# ADC_MUX.net
KiCad netlist of a schematic drawn in Altium Designer
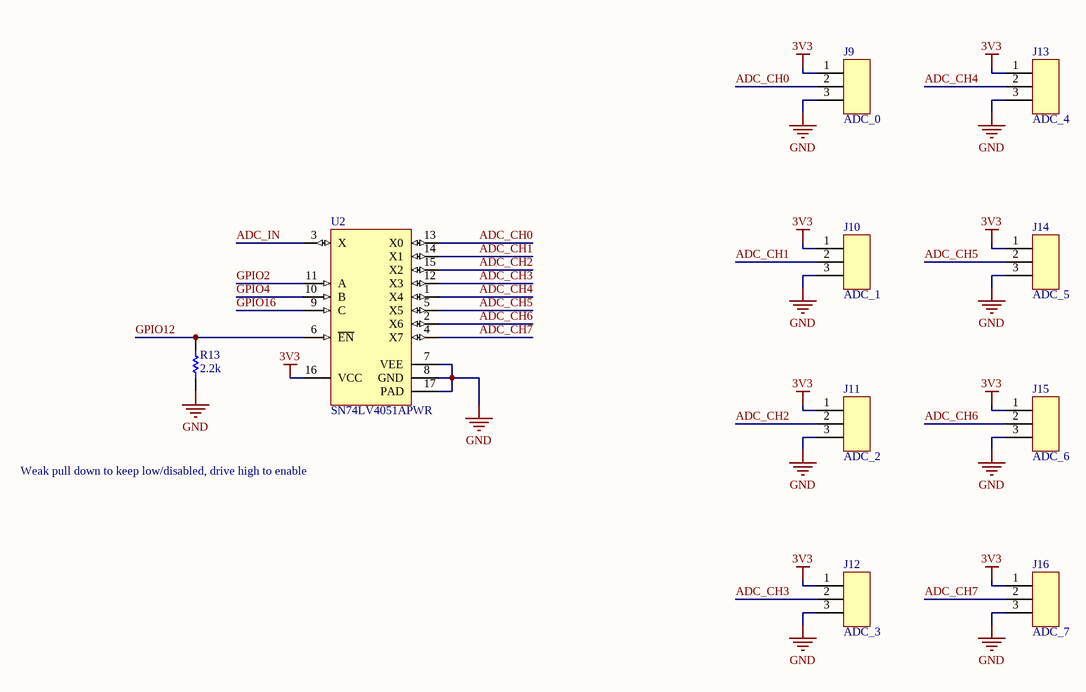
[diagram p0: ADC_MUX.SchDoc]

(export (version "E")
  (design (tool "Eeschema 10.0.6"))
  (components
    (comp (ref "J9")
      (value "ADC_0")
      (footprint "PCB-s0hfil65plaomi4ibvcw-1")
      (description "THT Vertical Pin Header WR-PHD, Pitch 2.54 mm, Single Row, 3 pins")
      (libsource (lib "CommunityVault") (part "SYM-8a90426ffa175557-17"))
    )
    (comp (ref "J10")
      (value "ADC_1")
      (footprint "PCB-s0hfil65plaomi4ibvcw-1")
      (description "THT Vertical Pin Header WR-PHD, Pitch 2.54 mm, Single Row, 3 pins")
      (libsource (lib "CommunityVault") (part "SYM-8a90426ffa175557-17"))
    )
    (comp (ref "J11")
      (value "ADC_2")
      (footprint "PCB-s0hfil65plaomi4ibvcw-1")
      (description "THT Vertical Pin Header WR-PHD, Pitch 2.54 mm, Single Row, 3 pins")
      (libsource (lib "CommunityVault") (part "SYM-8a90426ffa175557-17"))
    )
    (comp (ref "J12")
      (value "ADC_3")
      (footprint "PCB-s0hfil65plaomi4ibvcw-1")
      (description "THT Vertical Pin Header WR-PHD, Pitch 2.54 mm, Single Row, 3 pins")
      (libsource (lib "CommunityVault") (part "SYM-8a90426ffa175557-17"))
    )
    (comp (ref "J13")
      (value "ADC_4")
      (footprint "PCB-s0hfil65plaomi4ibvcw-1")
      (description "THT Vertical Pin Header WR-PHD, Pitch 2.54 mm, Single Row, 3 pins")
      (libsource (lib "CommunityVault") (part "SYM-8a90426ffa175557-17"))
    )
    (comp (ref "J14")
      (value "ADC_5")
      (footprint "PCB-s0hfil65plaomi4ibvcw-1")
      (description "THT Vertical Pin Header WR-PHD, Pitch 2.54 mm, Single Row, 3 pins")
      (libsource (lib "CommunityVault") (part "SYM-8a90426ffa175557-17"))
    )
    (comp (ref "J15")
      (value "ADC_6")
      (footprint "PCB-s0hfil65plaomi4ibvcw-1")
      (description "THT Vertical Pin Header WR-PHD, Pitch 2.54 mm, Single Row, 3 pins")
      (libsource (lib "CommunityVault") (part "SYM-8a90426ffa175557-17"))
    )
    (comp (ref "J16")
      (value "ADC_7")
      (footprint "PCB-s0hfil65plaomi4ibvcw-1")
      (description "THT Vertical Pin Header WR-PHD, Pitch 2.54 mm, Single Row, 3 pins")
      (libsource (lib "CommunityVault") (part "SYM-8a90426ffa175557-17"))
    )
    (comp (ref "R13")
      (value "2.2k")
      (footprint "PCB-2t5lv6a742zfbi3344hk-1")
      (description "Res, AEC-Q200, Thick Film, 2K2, 5%, 0603")
      (fields (field (name "MANUFACTURER PART NUMBER") "CRGCQ0603J2K2"))
      (libsource (lib "CommunityVault") (part "SYM-ce770211389311b0-1"))
    )
    (comp (ref "U2")
      (value "SN74LV4051APWR")
      (footprint "PCB-s2tlwx05pg4l7j3eq4ax-1")
      (description "5-V, 8: 1, 1-channel general-purpose analog multiplexer 16-TSSOP -40 to 85")
      (libsource (lib "FavoritesLibrary") (part "SYM-2f9ae6973f1af05d-2"))
    )
  )
  (nets
    (net (code "1") (name "/ADC_CH0") (class "Default")
      (node (ref "J9") (pin "2") (pinfunction "2_2") (pintype "passive"))
      (node (ref "U2") (pin "13") (pinfunction "X0_13") (pintype "bidirectional"))
    )
    (net (code "2") (name "/ADC_CH1") (class "Default")
      (node (ref "J10") (pin "2") (pinfunction "2_2") (pintype "passive"))
      (node (ref "U2") (pin "14") (pinfunction "X1_14") (pintype "bidirectional"))
    )
    (net (code "3") (name "/ADC_CH2") (class "Default")
      (node (ref "J11") (pin "2") (pinfunction "2_2") (pintype "passive"))
      (node (ref "U2") (pin "15") (pinfunction "X2_15") (pintype "bidirectional"))
    )
    (net (code "4") (name "/ADC_CH3") (class "Default")
      (node (ref "J12") (pin "2") (pinfunction "2_2") (pintype "passive"))
      (node (ref "U2") (pin "12") (pinfunction "X3_12") (pintype "bidirectional"))
    )
    (net (code "5") (name "/ADC_CH4") (class "Default")
      (node (ref "J13") (pin "2") (pinfunction "2_2") (pintype "passive"))
      (node (ref "U2") (pin "1") (pinfunction "X4_1") (pintype "bidirectional"))
    )
    (net (code "6") (name "/ADC_CH5") (class "Default")
      (node (ref "J14") (pin "2") (pinfunction "2_2") (pintype "passive"))
      (node (ref "U2") (pin "5") (pinfunction "X5_5") (pintype "bidirectional"))
    )
    (net (code "7") (name "/ADC_CH6") (class "Default")
      (node (ref "J15") (pin "2") (pinfunction "2_2") (pintype "passive"))
      (node (ref "U2") (pin "2") (pinfunction "X6_2") (pintype "bidirectional"))
    )
    (net (code "8") (name "/ADC_CH7") (class "Default")
      (node (ref "J16") (pin "2") (pinfunction "2_2") (pintype "passive"))
      (node (ref "U2") (pin "4") (pinfunction "X7_4") (pintype "bidirectional"))
    )
    (net (code "9") (name "/ADC_IN") (class "Default")
      (node (ref "U2") (pin "3") (pinfunction "X_3") (pintype "bidirectional"))
    )
    (net (code "10") (name "/GPIO2") (class "Default")
      (node (ref "U2") (pin "11") (pinfunction "A_11") (pintype "input"))
    )
    (net (code "11") (name "/GPIO4") (class "Default")
      (node (ref "U2") (pin "10") (pinfunction "B_10") (pintype "input"))
    )
    (net (code "12") (name "/GPIO12") (class "Default")
      (node (ref "R13") (pin "2") (pinfunction "2_2") (pintype "passive"))
      (node (ref "U2") (pin "6") (pinfunction "~{EN}_6") (pintype "input"))
    )
    (net (code "13") (name "/GPIO16") (class "Default")
      (node (ref "U2") (pin "9") (pinfunction "C_9") (pintype "input"))
    )
    (net (code "14") (name "3V3") (class "Default")
      (node (ref "J10") (pin "1") (pinfunction "1_1") (pintype "passive"))
      (node (ref "J11") (pin "1") (pinfunction "1_1") (pintype "passive"))
      (node (ref "J12") (pin "1") (pinfunction "1_1") (pintype "passive"))
      (node (ref "J13") (pin "1") (pinfunction "1_1") (pintype "passive"))
      (node (ref "J14") (pin "1") (pinfunction "1_1") (pintype "passive"))
      (node (ref "J15") (pin "1") (pinfunction "1_1") (pintype "passive"))
      (node (ref "J16") (pin "1") (pinfunction "1_1") (pintype "passive"))
      (node (ref "J9") (pin "1") (pinfunction "1_1") (pintype "passive"))
      (node (ref "U2") (pin "16") (pinfunction "VCC_16") (pintype "power_in"))
    )
    (net (code "15") (name "GND") (class "Default")
      (node (ref "J10") (pin "3") (pinfunction "3_3") (pintype "passive"))
      (node (ref "J11") (pin "3") (pinfunction "3_3") (pintype "passive"))
      (node (ref "J12") (pin "3") (pinfunction "3_3") (pintype "passive"))
      (node (ref "J13") (pin "3") (pinfunction "3_3") (pintype "passive"))
      (node (ref "J14") (pin "3") (pinfunction "3_3") (pintype "passive"))
      (node (ref "J15") (pin "3") (pinfunction "3_3") (pintype "passive"))
      (node (ref "J16") (pin "3") (pinfunction "3_3") (pintype "passive"))
      (node (ref "J9") (pin "3") (pinfunction "3_3") (pintype "passive"))
      (node (ref "R13") (pin "1") (pinfunction "1_1") (pintype "passive"))
      (node (ref "U2") (pin "17") (pinfunction "PAD_17") (pintype "power_in"))
      (node (ref "U2") (pin "7") (pinfunction "VEE_7") (pintype "power_in"))
      (node (ref "U2") (pin "8") (pinfunction "GND_8") (pintype "power_in"))
    )
  )
)
